# Sp_jkova_ka_3000_MK_I.net
KiCad netlist of a schematic drawn in EAGLE
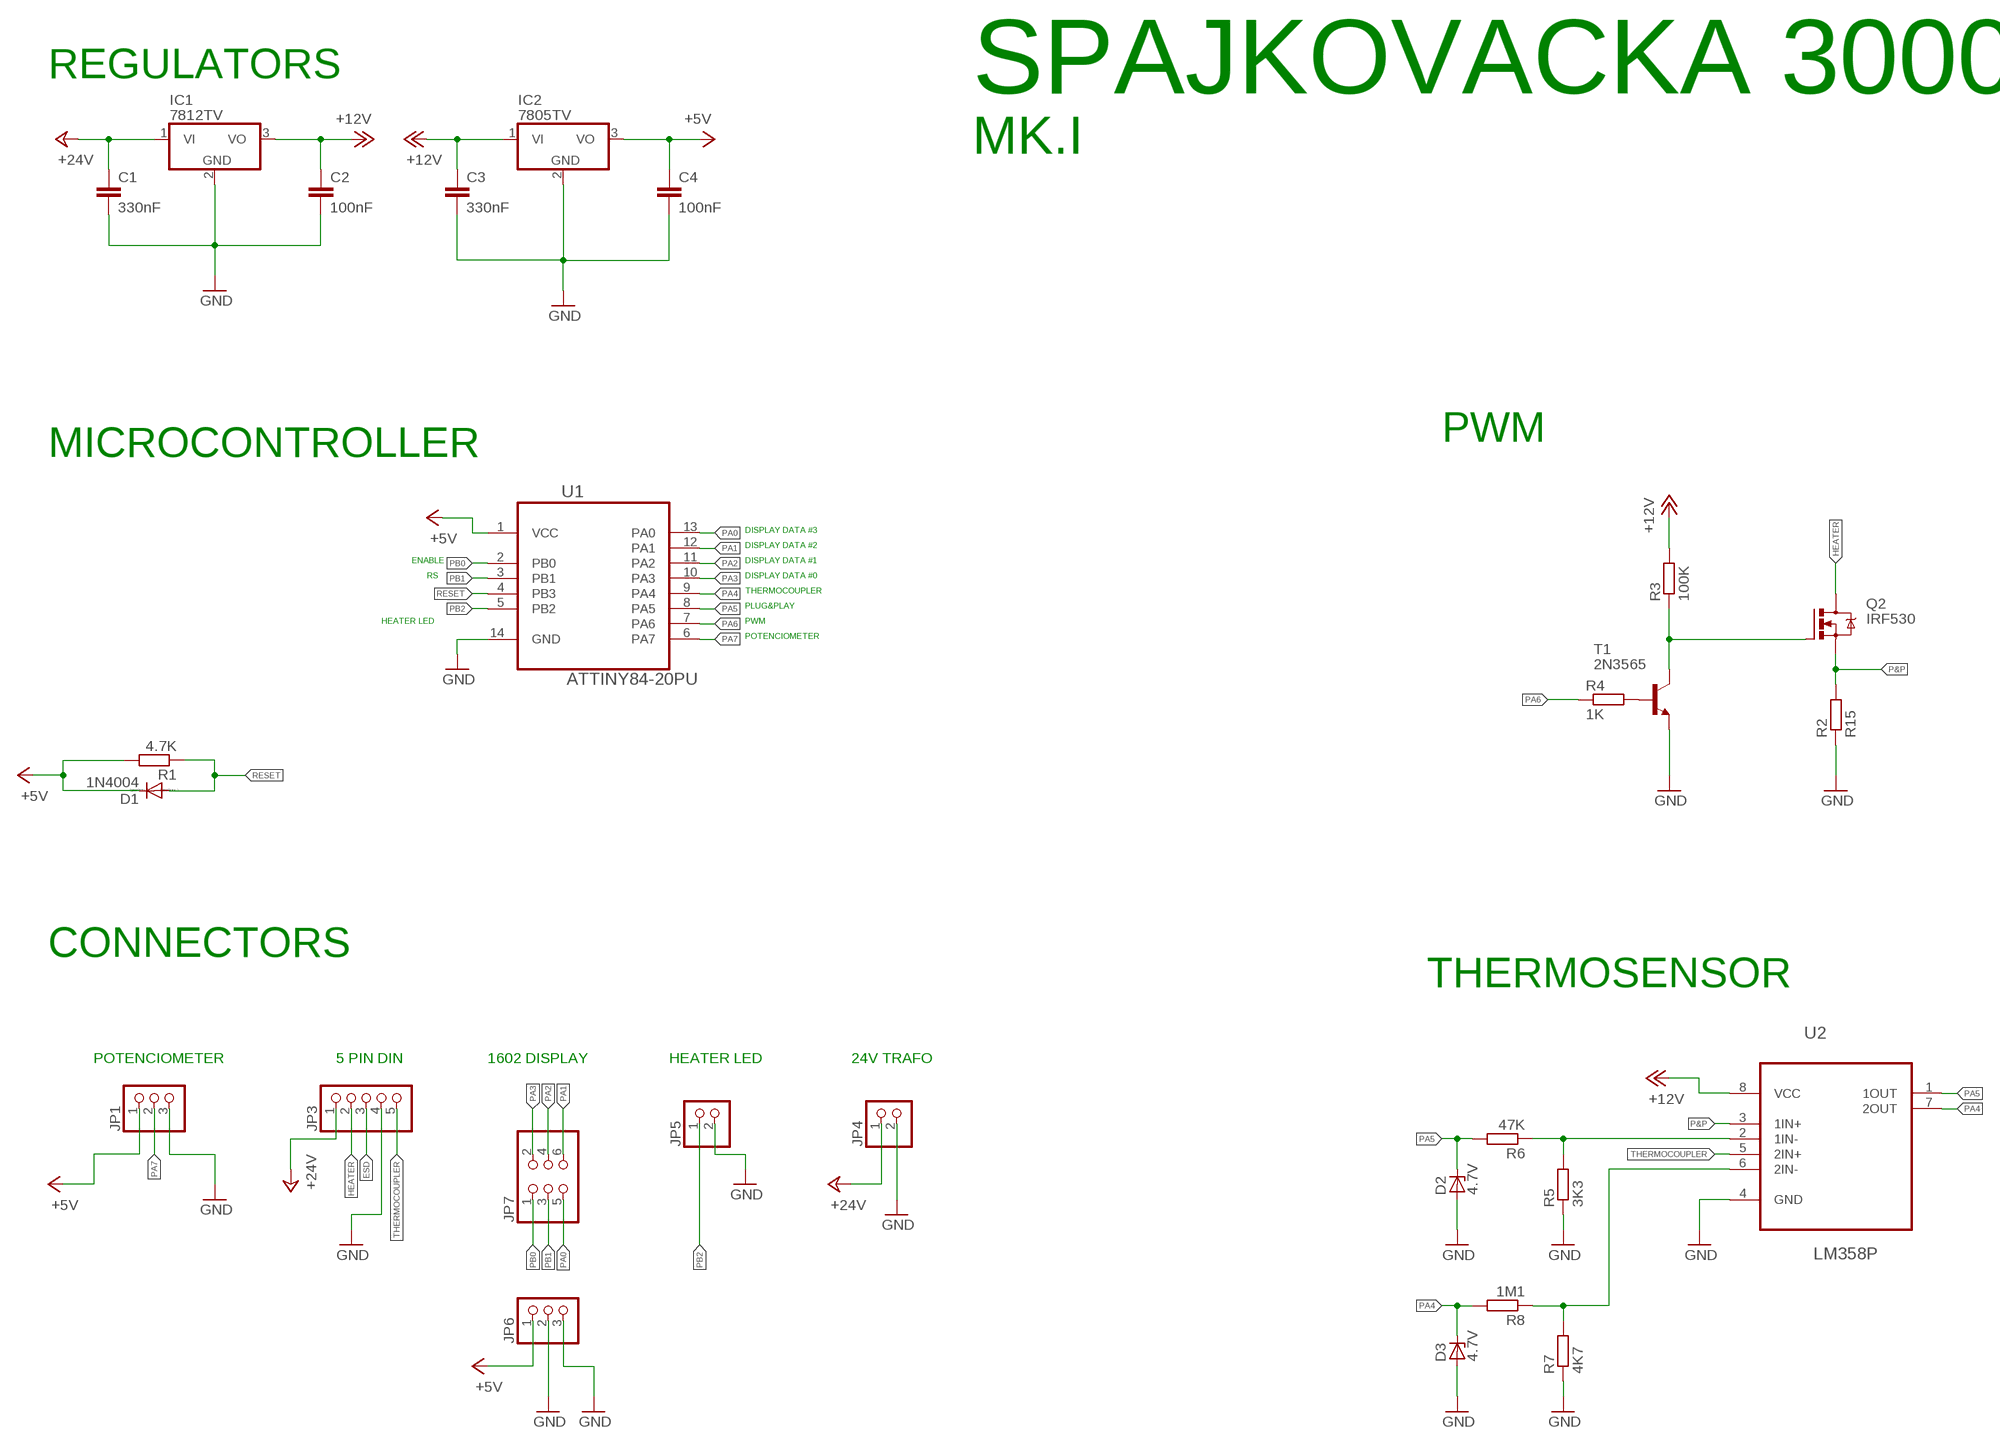
[diagram p0: schematic, sheet 1]

(export (version "E")
  (design (tool "Eeschema 10.0.6"))
  (components
    (comp (ref "C1")
      (value "330nF")
      (footprint "eagle-import:C025-024X044")
      (libsource (lib "eagle-import") (part "C-EU025-024X044"))
    )
    (comp (ref "C2")
      (value "100nF")
      (footprint "eagle-import:C025-024X044")
      (libsource (lib "eagle-import") (part "C-EU025-024X044"))
    )
    (comp (ref "C3")
      (value "330nF")
      (footprint "eagle-import:C025-024X044")
      (libsource (lib "eagle-import") (part "C-EU025-024X044"))
    )
    (comp (ref "C4")
      (value "100nF")
      (footprint "eagle-import:C025-024X044")
      (libsource (lib "eagle-import") (part "C-EU025-024X044"))
    )
    (comp (ref "D1")
      (value "1N4004")
      (footprint "eagle-import:DO41-10")
      (libsource (lib "eagle-import") (part "1N4004"))
    )
    (comp (ref "D2")
      (value "4.7V")
      (footprint "eagle-import:DO41Z10")
      (libsource (lib "eagle-import") (part "ZENER-DIODEDO41Z10"))
    )
    (comp (ref "D3")
      (value "4.7V")
      (footprint "eagle-import:DO41Z10")
      (libsource (lib "eagle-import") (part "ZENER-DIODEDO41Z10"))
    )
    (comp (ref "IC1")
      (value "7812TV")
      (footprint "eagle-import:TO220V")
      (libsource (lib "eagle-import") (part "78TV12"))
    )
    (comp (ref "IC2")
      (value "7805TV")
      (footprint "eagle-import:TO220V")
      (libsource (lib "eagle-import") (part "78TV05"))
    )
    (comp (ref "JP1")
      (value "PINHD-1X3")
      (footprint "eagle-import:1X03")
      (libsource (lib "eagle-import") (part "PINHD-1X3"))
    )
    (comp (ref "JP3")
      (value "PINHD-1X5")
      (footprint "eagle-import:1X05")
      (libsource (lib "eagle-import") (part "PINHD-1X5"))
    )
    (comp (ref "JP4")
      (value "PINHD-1X2")
      (footprint "eagle-import:1X02")
      (libsource (lib "eagle-import") (part "PINHD-1X2"))
    )
    (comp (ref "JP5")
      (value "PINHD-1X2")
      (footprint "eagle-import:1X02")
      (libsource (lib "eagle-import") (part "PINHD-1X2"))
    )
    (comp (ref "JP6")
      (value "PINHD-1X3")
      (footprint "eagle-import:1X03")
      (libsource (lib "eagle-import") (part "PINHD-1X3"))
    )
    (comp (ref "JP7")
      (value "PINHD-2X3")
      (footprint "eagle-import:2X03")
      (libsource (lib "eagle-import") (part "PINHD-2X3"))
    )
    (comp (ref "Q2")
      (value "IRF530")
      (footprint "eagle-import:TO220BV")
      (libsource (lib "eagle-import") (part "IRF530"))
    )
    (comp (ref "R1")
      (value "4.7K")
      (footprint "eagle-import:0207_10")
      (libsource (lib "eagle-import") (part "R-EU_0207/10"))
    )
    (comp (ref "R2")
      (value "R15")
      (footprint "eagle-import:0922_22")
      (libsource (lib "eagle-import") (part "R-EU_0922/22"))
    )
    (comp (ref "R3")
      (value "100K")
      (footprint "eagle-import:0207_10")
      (libsource (lib "eagle-import") (part "R-EU_0207/10"))
    )
    (comp (ref "R4")
      (value "1K")
      (footprint "eagle-import:0207_10")
      (libsource (lib "eagle-import") (part "R-EU_0207/10"))
    )
    (comp (ref "R5")
      (value "3K3")
      (footprint "eagle-import:0207_10")
      (libsource (lib "eagle-import") (part "R-EU_0207/10"))
    )
    (comp (ref "R6")
      (value "47K")
      (footprint "eagle-import:0207_10")
      (libsource (lib "eagle-import") (part "R-EU_0207/10"))
    )
    (comp (ref "R7")
      (value "4K7")
      (footprint "eagle-import:0207_10")
      (libsource (lib "eagle-import") (part "R-EU_0207/10"))
    )
    (comp (ref "R8")
      (value "1M1")
      (footprint "eagle-import:0207_10")
      (libsource (lib "eagle-import") (part "R-EU_0207/10"))
    )
    (comp (ref "T1")
      (value "2N3565")
      (footprint "eagle-import:TO92")
      (libsource (lib "eagle-import") (part "2N3565"))
    )
    (comp (ref "U1")
      (value "ATTINY84-20PU")
      (footprint "eagle-import:DIP254P762X533-14")
      (libsource (lib "eagle-import") (part "ATTINY84-20PU"))
    )
    (comp (ref "U2")
      (value "LM358P")
      (footprint "eagle-import:DIP254P762X508-8")
      (libsource (lib "eagle-import") (part "LM358P"))
    )
  )
  (nets
    (net (code "1") (name "+5V") (class "Default")
      (node (ref "C4") (pin "1") (pinfunction "1_1") (pintype "passive"))
      (node (ref "D1") (pin "C") (pinfunction "C_C") (pintype "passive"))
      (node (ref "IC2") (pin "3") (pinfunction "VO_3") (pintype "passive"))
      (node (ref "JP1") (pin "1") (pinfunction "1_1") (pintype "passive"))
      (node (ref "JP6") (pin "1") (pinfunction "1_1") (pintype "passive"))
      (node (ref "R1") (pin "2") (pinfunction "2_2") (pintype "passive"))
      (node (ref "U1") (pin "1") (pinfunction "VCC_1") (pintype "power_in"))
    )
    (net (code "2") (name "+12V") (class "Default")
      (node (ref "C2") (pin "1") (pinfunction "1_1") (pintype "passive"))
      (node (ref "C3") (pin "1") (pinfunction "1_1") (pintype "passive"))
      (node (ref "IC1") (pin "3") (pinfunction "VO_3") (pintype "passive"))
      (node (ref "IC2") (pin "1") (pinfunction "VI_1") (pintype "input"))
      (node (ref "R3") (pin "2") (pinfunction "2_2") (pintype "passive"))
      (node (ref "U2") (pin "8") (pinfunction "VCC_8") (pintype "power_in"))
    )
    (net (code "3") (name "+24V") (class "Default")
      (node (ref "C1") (pin "1") (pinfunction "1_1") (pintype "passive"))
      (node (ref "IC1") (pin "1") (pinfunction "VI_1") (pintype "input"))
      (node (ref "JP3") (pin "1") (pinfunction "1_1") (pintype "passive"))
      (node (ref "JP4") (pin "1") (pinfunction "1_1") (pintype "passive"))
    )
    (net (code "4") (name "ESD") (class "Default")
      (node (ref "JP3") (pin "3") (pinfunction "3_3") (pintype "passive"))
    )
    (net (code "5") (name "GND") (class "Default")
      (node (ref "C1") (pin "2") (pinfunction "2_2") (pintype "passive"))
      (node (ref "C2") (pin "2") (pinfunction "2_2") (pintype "passive"))
      (node (ref "C3") (pin "2") (pinfunction "2_2") (pintype "passive"))
      (node (ref "C4") (pin "2") (pinfunction "2_2") (pintype "passive"))
      (node (ref "D2") (pin "A") (pinfunction "A_A") (pintype "passive"))
      (node (ref "D3") (pin "A") (pinfunction "A_A") (pintype "passive"))
      (node (ref "IC1") (pin "2") (pinfunction "GND_2") (pintype "passive"))
      (node (ref "IC2") (pin "2") (pinfunction "GND_2") (pintype "passive"))
      (node (ref "JP1") (pin "3") (pinfunction "3_3") (pintype "passive"))
      (node (ref "JP3") (pin "4") (pinfunction "4_4") (pintype "passive"))
      (node (ref "JP4") (pin "2") (pinfunction "2_2") (pintype "passive"))
      (node (ref "JP5") (pin "2") (pinfunction "2_2") (pintype "passive"))
      (node (ref "JP6") (pin "2") (pinfunction "2_2") (pintype "passive"))
      (node (ref "JP6") (pin "3") (pinfunction "3_3") (pintype "passive"))
      (node (ref "R2") (pin "1") (pinfunction "1_1") (pintype "passive"))
      (node (ref "R5") (pin "1") (pinfunction "1_1") (pintype "passive"))
      (node (ref "R7") (pin "1") (pinfunction "1_1") (pintype "passive"))
      (node (ref "T1") (pin "3") (pinfunction "E_3") (pintype "passive"))
      (node (ref "U1") (pin "14") (pinfunction "GND_14") (pintype "passive"))
      (node (ref "U2") (pin "4") (pinfunction "GND_4") (pintype "power_in"))
    )
    (net (code "6") (name "HEATER") (class "Default")
      (node (ref "JP3") (pin "2") (pinfunction "2_2") (pintype "passive"))
      (node (ref "Q2") (pin "D") (pinfunction "D_D") (pintype "passive"))
    )
    (net (code "7") (name "Net-(T1-B)") (class "Default")
      (node (ref "R4") (pin "2") (pinfunction "2_2") (pintype "passive"))
      (node (ref "T1") (pin "2") (pinfunction "B_2") (pintype "passive"))
    )
    (net (code "8") (name "Net-(T1-C)") (class "Default")
      (node (ref "Q2") (pin "G") (pinfunction "G_G") (pintype "passive"))
      (node (ref "R3") (pin "1") (pinfunction "1_1") (pintype "passive"))
      (node (ref "T1") (pin "1") (pinfunction "C_1") (pintype "passive"))
    )
    (net (code "9") (name "Net-(U2-1IN-)") (class "Default")
      (node (ref "R5") (pin "2") (pinfunction "2_2") (pintype "passive"))
      (node (ref "R6") (pin "1") (pinfunction "1_1") (pintype "passive"))
      (node (ref "U2") (pin "2") (pinfunction "1IN-_2") (pintype "input"))
    )
    (net (code "10") (name "Net-(U2-2IN-)") (class "Default")
      (node (ref "R7") (pin "2") (pinfunction "2_2") (pintype "passive"))
      (node (ref "R8") (pin "1") (pinfunction "1_1") (pintype "passive"))
      (node (ref "U2") (pin "6") (pinfunction "2IN-_6") (pintype "input"))
    )
    (net (code "11") (name "P&P") (class "Default")
      (node (ref "Q2") (pin "S") (pinfunction "S_S") (pintype "passive"))
      (node (ref "R2") (pin "2") (pinfunction "2_2") (pintype "passive"))
      (node (ref "U2") (pin "3") (pinfunction "1IN+_3") (pintype "input"))
    )
    (net (code "12") (name "PA0") (class "Default")
      (node (ref "JP7") (pin "5") (pinfunction "5_5") (pintype "passive"))
      (node (ref "U1") (pin "13") (pinfunction "PA0_13") (pintype "bidirectional"))
    )
    (net (code "13") (name "PA1") (class "Default")
      (node (ref "JP7") (pin "6") (pinfunction "6_6") (pintype "passive"))
      (node (ref "U1") (pin "12") (pinfunction "PA1_12") (pintype "bidirectional"))
    )
    (net (code "14") (name "PA2") (class "Default")
      (node (ref "JP7") (pin "4") (pinfunction "4_4") (pintype "passive"))
      (node (ref "U1") (pin "11") (pinfunction "PA2_11") (pintype "bidirectional"))
    )
    (net (code "15") (name "PA3") (class "Default")
      (node (ref "JP7") (pin "2") (pinfunction "2_2") (pintype "passive"))
      (node (ref "U1") (pin "10") (pinfunction "PA3_10") (pintype "bidirectional"))
    )
    (net (code "16") (name "PA4") (class "Default")
      (node (ref "D3") (pin "C") (pinfunction "C_C") (pintype "passive"))
      (node (ref "R8") (pin "2") (pinfunction "2_2") (pintype "passive"))
      (node (ref "U1") (pin "9") (pinfunction "PA4_9") (pintype "bidirectional"))
      (node (ref "U2") (pin "7") (pinfunction "2OUT_7") (pintype "output"))
    )
    (net (code "17") (name "PA5") (class "Default")
      (node (ref "D2") (pin "C") (pinfunction "C_C") (pintype "passive"))
      (node (ref "R6") (pin "2") (pinfunction "2_2") (pintype "passive"))
      (node (ref "U1") (pin "8") (pinfunction "PA5_8") (pintype "bidirectional"))
      (node (ref "U2") (pin "1") (pinfunction "1OUT_1") (pintype "output"))
    )
    (net (code "18") (name "PA6") (class "Default")
      (node (ref "R4") (pin "1") (pinfunction "1_1") (pintype "passive"))
      (node (ref "U1") (pin "7") (pinfunction "PA6_7") (pintype "bidirectional"))
    )
    (net (code "19") (name "PA7") (class "Default")
      (node (ref "JP1") (pin "2") (pinfunction "2_2") (pintype "passive"))
      (node (ref "U1") (pin "6") (pinfunction "PA7_6") (pintype "bidirectional"))
    )
    (net (code "20") (name "PB0") (class "Default")
      (node (ref "JP7") (pin "1") (pinfunction "1_1") (pintype "passive"))
      (node (ref "U1") (pin "2") (pinfunction "PB0_2") (pintype "bidirectional"))
    )
    (net (code "21") (name "PB1") (class "Default")
      (node (ref "JP7") (pin "3") (pinfunction "3_3") (pintype "passive"))
      (node (ref "U1") (pin "3") (pinfunction "PB1_3") (pintype "bidirectional"))
    )
    (net (code "22") (name "PB2") (class "Default")
      (node (ref "JP5") (pin "1") (pinfunction "1_1") (pintype "passive"))
      (node (ref "U1") (pin "5") (pinfunction "PB2_5") (pintype "bidirectional"))
    )
    (net (code "23") (name "RESET") (class "Default")
      (node (ref "D1") (pin "A") (pinfunction "A_A") (pintype "passive"))
      (node (ref "R1") (pin "1") (pinfunction "1_1") (pintype "passive"))
      (node (ref "U1") (pin "4") (pinfunction "PB3_4") (pintype "bidirectional"))
    )
    (net (code "24") (name "THERMOCOUPLER") (class "Default")
      (node (ref "JP3") (pin "5") (pinfunction "5_5") (pintype "passive"))
      (node (ref "U2") (pin "5") (pinfunction "2IN+_5") (pintype "input"))
    )
  )
)
